# 16-channel-EEG-SCH.net
KiCad netlist of a schematic drawn in Altium Designer
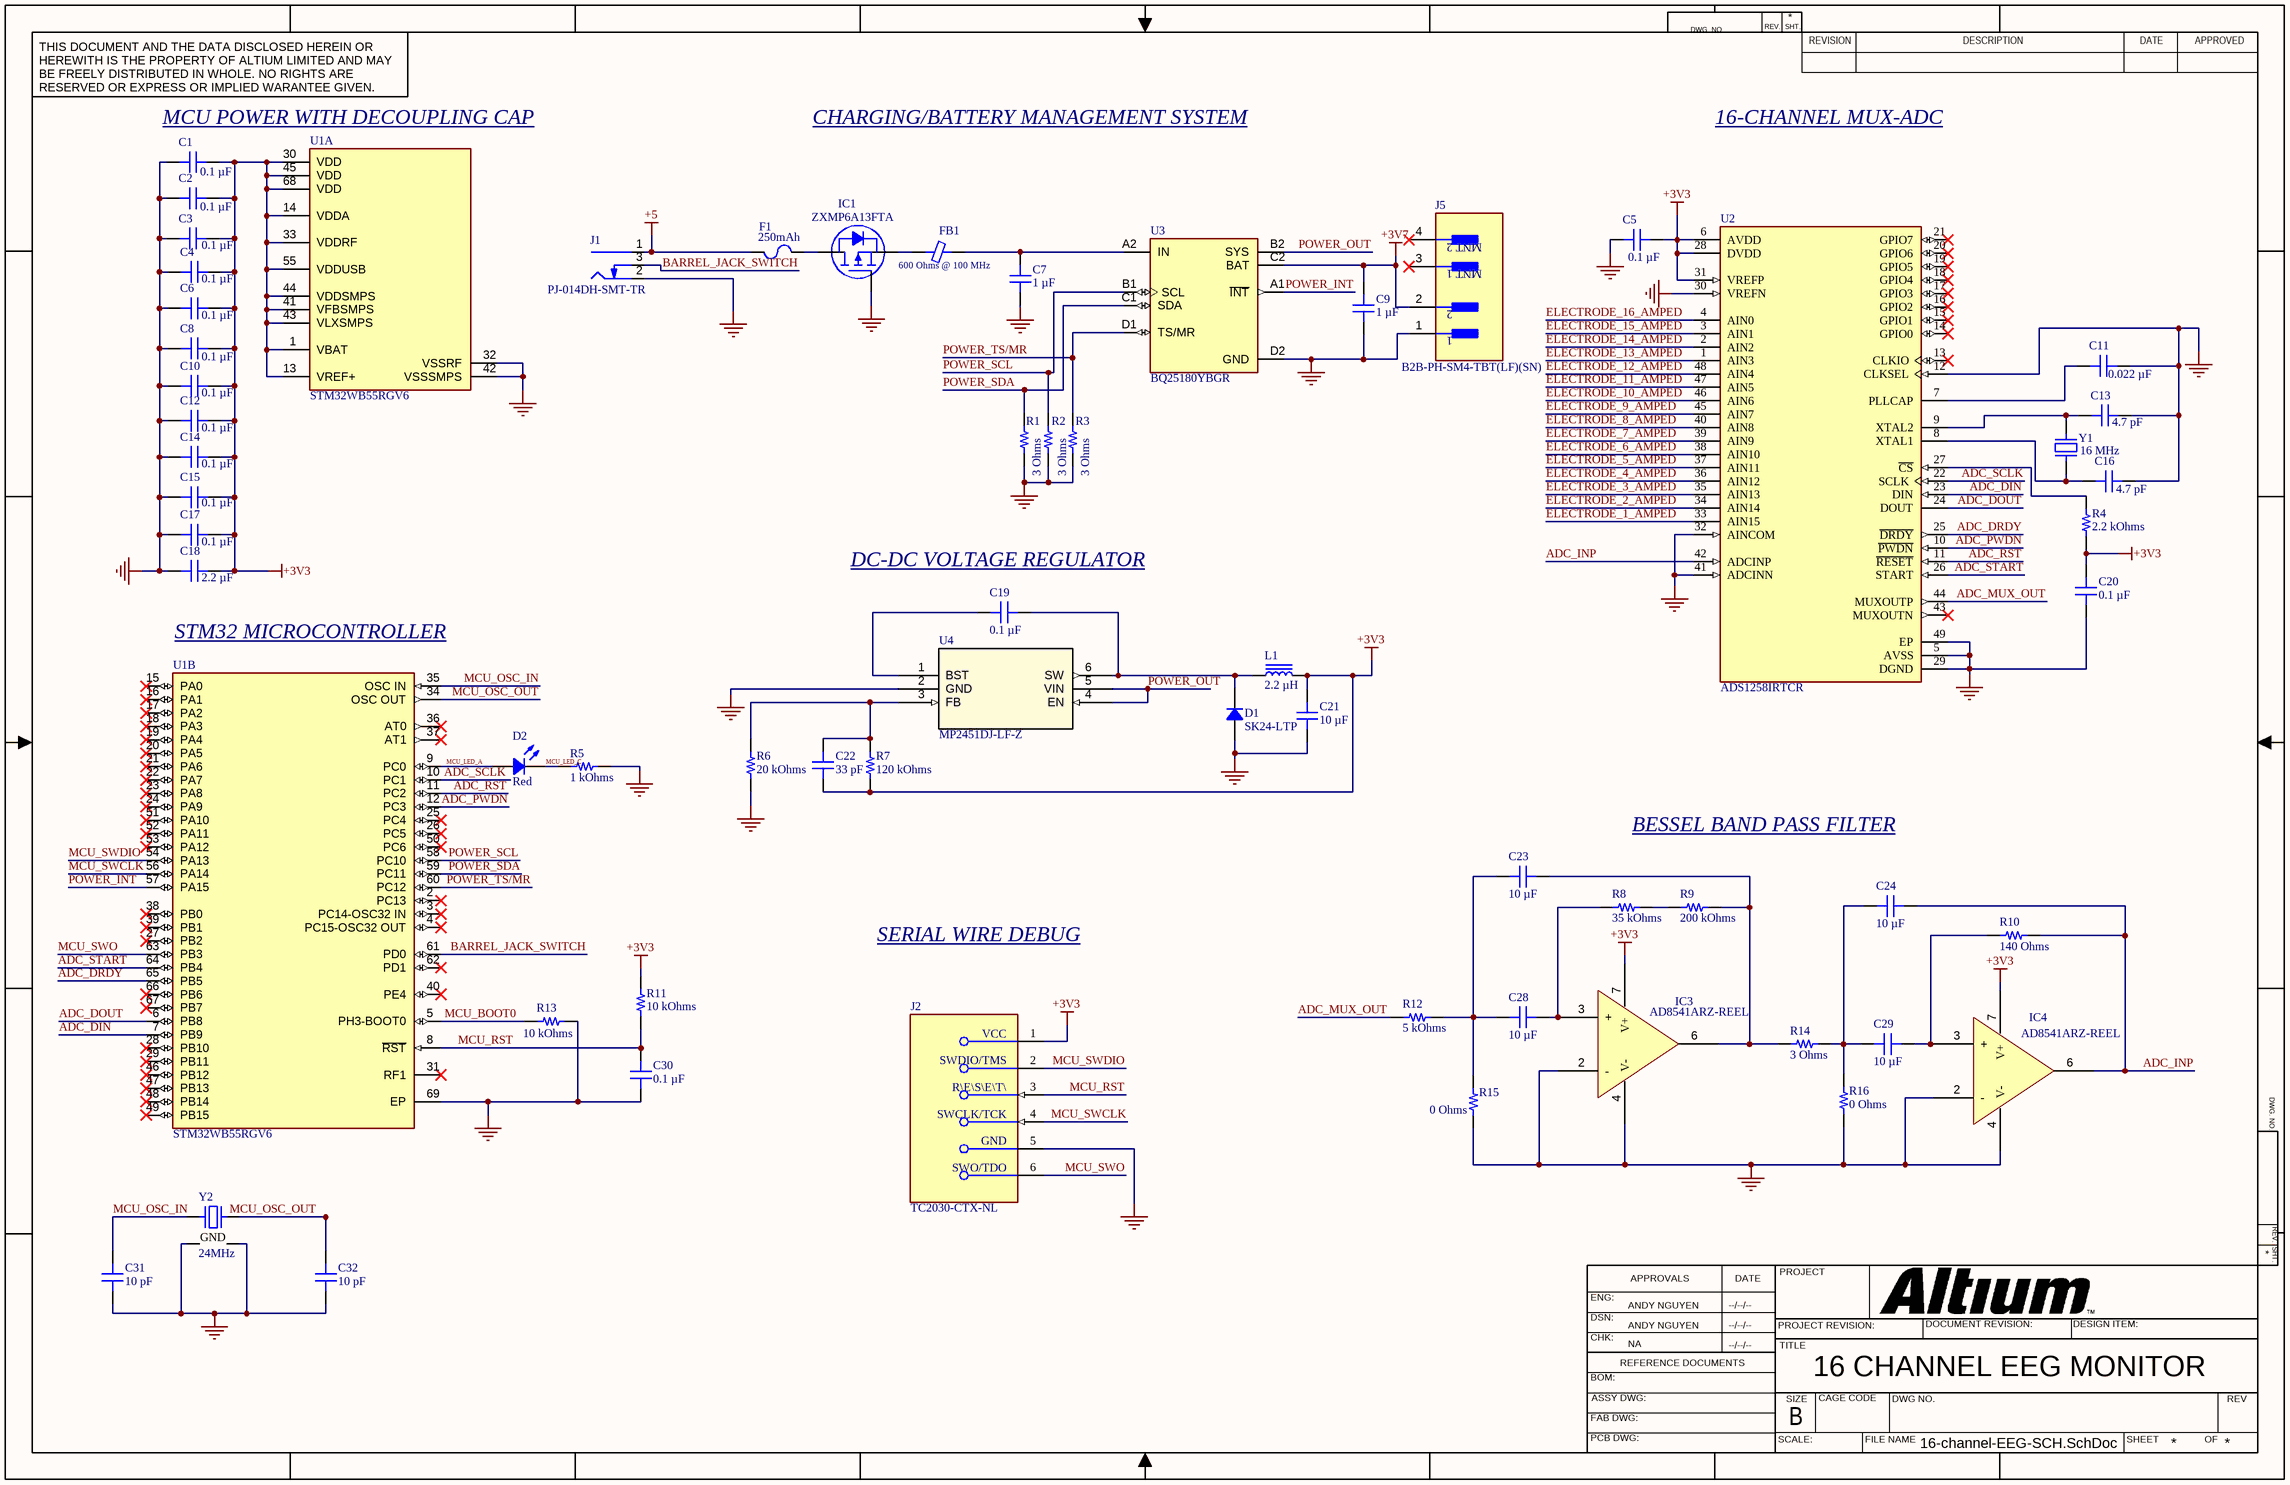
[diagram p0: 16-channel-EEG-SCH.SchDoc]

(export (version "E")
  (design (tool "Eeschema 10.0.6"))
  (components
    (comp (ref "C1")
      (value "0.1 µF")
      (footprint "CAP 0402_1005")
      (description "CAP CER 0402 0.1UF 16V X7R 10%")
      (fields (field (name "PART NUMBER") "C0402C104K4RECAUTO") (field (name "MANUFACTURER") "KEMET"))
      (libsource (lib "Celestial Altium Library - altium_library") (part "Capacitor"))
    )
    (comp (ref "C2")
      (value "0.1 µF")
      (footprint "CAP 0402_1005")
      (description "CAP CER 0402 0.1UF 16V X7R 10%")
      (fields (field (name "PART NUMBER") "C0402C104K4RECAUTO") (field (name "MANUFACTURER") "KEMET"))
      (libsource (lib "Celestial Altium Library - altium_library") (part "Capacitor"))
    )
    (comp (ref "C3")
      (value "0.1 µF")
      (footprint "CAP 0402_1005")
      (description "CAP CER 0402 0.1UF 16V X7R 10%")
      (fields (field (name "PART NUMBER") "C0402C104K4RECAUTO") (field (name "MANUFACTURER") "KEMET"))
      (libsource (lib "Celestial Altium Library - altium_library") (part "Capacitor"))
    )
    (comp (ref "C4")
      (value "0.1 µF")
      (footprint "CAP 0402_1005")
      (description "CAP CER 0402 0.1UF 16V X7R 10%")
      (fields (field (name "PART NUMBER") "C0402C104K4RECAUTO") (field (name "MANUFACTURER") "KEMET"))
      (libsource (lib "Celestial Altium Library - altium_library") (part "Capacitor"))
    )
    (comp (ref "C5")
      (value "0.1 µF")
      (footprint "CAP 0402_1005")
      (description "CAP CER 0402 0.1UF 16V X7R 10%")
      (fields (field (name "PART NUMBER") "C0402C104K4RECAUTO") (field (name "MANUFACTURER") "KEMET"))
      (libsource (lib "Celestial Altium Library - altium_library") (part "Capacitor"))
    )
    (comp (ref "C6")
      (value "0.1 µF")
      (footprint "CAP 0402_1005")
      (description "CAP CER 0402 0.1UF 16V X7R 10%")
      (fields (field (name "PART NUMBER") "C0402C104K4RECAUTO") (field (name "MANUFACTURER") "KEMET"))
      (libsource (lib "Celestial Altium Library - altium_library") (part "Capacitor"))
    )
    (comp (ref "C7")
      (value "1 µF")
      (footprint "CAP 0402_1005")
      (description "CAP CER 1UF 35V X5R 0402")
      (fields
        (field (name "PART NUMBER") "GRM155R6YA105KE11D")
        (field (name "MANUFACTURER") "Murata Electronics")
      )
      (libsource (lib "Celestial Altium Library - altium_library") (part "Capacitor"))
    )
    (comp (ref "C8")
      (value "0.1 µF")
      (footprint "CAP 0402_1005")
      (description "CAP CER 0402 0.1UF 16V X7R 10%")
      (fields (field (name "PART NUMBER") "C0402C104K4RECAUTO") (field (name "MANUFACTURER") "KEMET"))
      (libsource (lib "Celestial Altium Library - altium_library") (part "Capacitor"))
    )
    (comp (ref "C9")
      (value "1 µF")
      (footprint "CAP 0402_1005")
      (description "CAP CER 1UF 35V X5R 0402")
      (fields
        (field (name "PART NUMBER") "GRM155R6YA105KE11D")
        (field (name "MANUFACTURER") "Murata Electronics")
      )
      (libsource (lib "Celestial Altium Library - altium_library") (part "Capacitor"))
    )
    (comp (ref "C10")
      (value "0.1 µF")
      (footprint "CAP 0402_1005")
      (description "CAP CER 0402 0.1UF 16V X7R 10%")
      (fields (field (name "PART NUMBER") "C0402C104K4RECAUTO") (field (name "MANUFACTURER") "KEMET"))
      (libsource (lib "Celestial Altium Library - altium_library") (part "Capacitor"))
    )
    (comp (ref "C11")
      (value "0.022 µF")
      (footprint "CAP 0402_1005")
      (description "CAP CER 0402 22NF 16V X7R 10%")
      (fields (field (name "PART NUMBER") "C0402C223K4RECAUTO") (field (name "MANUFACTURER") "KEMET"))
      (libsource (lib "Celestial Altium Library - altium_library") (part "Capacitor"))
    )
    (comp (ref "C12")
      (value "0.1 µF")
      (footprint "CAP 0402_1005")
      (description "CAP CER 0402 0.1UF 16V X7R 10%")
      (fields (field (name "PART NUMBER") "C0402C104K4RECAUTO") (field (name "MANUFACTURER") "KEMET"))
      (libsource (lib "Celestial Altium Library - altium_library") (part "Capacitor"))
    )
    (comp (ref "C13")
      (value "4.7 pF")
      (footprint "CAP 0402_1005")
      (description "CAP CER 4.7PF 16V C0G/NP0 0402")
      (fields (field (name "PART NUMBER") "885012005023") (field (name "MANUFACTURER") "Würth Elektronik"))
      (libsource (lib "Celestial Altium Library - altium_library") (part "Capacitor"))
    )
    (comp (ref "C14")
      (value "0.1 µF")
      (footprint "CAP 0402_1005")
      (description "CAP CER 0402 0.1UF 16V X7R 10%")
      (fields (field (name "PART NUMBER") "C0402C104K4RECAUTO") (field (name "MANUFACTURER") "KEMET"))
      (libsource (lib "Celestial Altium Library - altium_library") (part "Capacitor"))
    )
    (comp (ref "C15")
      (value "0.1 µF")
      (footprint "CAP 0402_1005")
      (description "CAP CER 0402 0.1UF 16V X7R 10%")
      (fields (field (name "PART NUMBER") "C0402C104K4RECAUTO") (field (name "MANUFACTURER") "KEMET"))
      (libsource (lib "Celestial Altium Library - altium_library") (part "Capacitor"))
    )
    (comp (ref "C16")
      (value "4.7 pF")
      (footprint "CAP 0402_1005")
      (description "CAP CER 4.7PF 16V C0G/NP0 0402")
      (fields (field (name "PART NUMBER") "885012005023") (field (name "MANUFACTURER") "Würth Elektronik"))
      (libsource (lib "Celestial Altium Library - altium_library") (part "Capacitor"))
    )
    (comp (ref "C17")
      (value "0.1 µF")
      (footprint "CAP 0402_1005")
      (description "CAP CER 0402 0.1UF 16V X7R 10%")
      (fields (field (name "PART NUMBER") "C0402C104K4RECAUTO") (field (name "MANUFACTURER") "KEMET"))
      (libsource (lib "Celestial Altium Library - altium_library") (part "Capacitor"))
    )
    (comp (ref "C18")
      (value "2.2 µF")
      (footprint "CAP 0603_1608")
      (description "CAP CER 2.2UF 16V Y5V 0603")
      (fields (field (name "PART NUMBER") "CC0603ZRY5V7BB225") (field (name "MANUFACTURER") "Yageo"))
      (libsource (lib "Celestial Altium Library - altium_library") (part "Capacitor"))
    )
    (comp (ref "C19")
      (value "0.1 µF")
      (footprint "CAP 0402_1005")
      (description "CAP CER 0.1UF 100V X5R 0402")
      (fields
        (field (name "PART NUMBER") "GRM155R62A104ME14D")
        (field (name "MANUFACTURER") "Murata Electronics")
      )
      (libsource (lib "Celestial Altium Library - altium_library") (part "Capacitor"))
    )
    (comp (ref "C20")
      (value "0.1 µF")
      (footprint "CAP 0402_1005")
      (description "CAP CER 0402 0.1UF 16V X7R 10%")
      (fields (field (name "PART NUMBER") "C0402C104K4RECAUTO") (field (name "MANUFACTURER") "KEMET"))
      (libsource (lib "Celestial Altium Library - altium_library") (part "Capacitor"))
    )
    (comp (ref "C21")
      (value "10 µF")
      (footprint "CAP 0402_1005")
      (description "CAP CER 10UF 10V X5R 0402")
      (fields
        (field (name "PART NUMBER") "CL05A106MP5NUNC")
        (field (name "MANUFACTURER") "Samsung Electro-Mechanics")
      )
      (libsource (lib "Celestial Altium Library - altium_library") (part "Capacitor"))
    )
    (comp (ref "C22")
      (value "33 pF")
      (footprint "CAP 0402_1005")
      (description "CAP CER 33PF 50V CH 0402")
      (fields (field (name "PART NUMBER") "UMK105CH330JVHF") (field (name "MANUFACTURER") "Taiyo Yuden"))
      (libsource (lib "Celestial Altium Library - altium_library") (part "Capacitor"))
    )
    (comp (ref "C23")
      (value "10 µF")
      (footprint "CAP 0402_1005")
      (description "CAP CER 10UF 10V X5R 0402")
      (fields
        (field (name "PART NUMBER") "CL05A106MP5NUNC")
        (field (name "MANUFACTURER") "Samsung Electro-Mechanics")
      )
      (libsource (lib "Celestial Altium Library - altium_library") (part "Capacitor"))
    )
    (comp (ref "C24")
      (value "10 µF")
      (footprint "CAP 0402_1005")
      (description "CAP CER 10UF 10V X5R 0402")
      (fields
        (field (name "PART NUMBER") "CL05A106MP5NUNC")
        (field (name "MANUFACTURER") "Samsung Electro-Mechanics")
      )
      (libsource (lib "Celestial Altium Library - altium_library") (part "Capacitor"))
    )
    (comp (ref "C28")
      (value "10 µF")
      (footprint "CAP 0402_1005")
      (description "CAP CER 10UF 10V X5R 0402")
      (fields
        (field (name "PART NUMBER") "CL05A106MP5NUNC")
        (field (name "MANUFACTURER") "Samsung Electro-Mechanics")
      )
      (libsource (lib "Celestial Altium Library - altium_library") (part "Capacitor"))
    )
    (comp (ref "C29")
      (value "10 µF")
      (footprint "CAP 0402_1005")
      (description "CAP CER 10UF 10V X5R 0402")
      (fields
        (field (name "PART NUMBER") "CL05A106MP5NUNC")
        (field (name "MANUFACTURER") "Samsung Electro-Mechanics")
      )
      (libsource (lib "Celestial Altium Library - altium_library") (part "Capacitor"))
    )
    (comp (ref "C30")
      (value "0.1 µF")
      (footprint "CAP 0402_1005")
      (description "CAP CER 100NF 10V X7R 0402")
      (fields
        (field (name "PART NUMBER") "CL05B104KP5VPNC")
        (field (name "MANUFACTURER") "Samsung Electro-Mechanics")
      )
      (libsource (lib "Celestial Altium Library - altium_library") (part "Capacitor"))
    )
    (comp (ref "C31")
      (value "10 pF")
      (footprint "CAP 0402_1005")
      (description "CAP CER 10PF 16V C0G/NP0 0402")
      (fields (field (name "PART NUMBER") "885012005025") (field (name "MANUFACTURER") "Würth Elektronik"))
      (libsource (lib "Celestial Altium Library - altium_library") (part "Capacitor"))
    )
    (comp (ref "C32")
      (value "10 pF")
      (footprint "CAP 0402_1005")
      (description "CAP CER 10PF 16V C0G/NP0 0402")
      (fields (field (name "PART NUMBER") "885012005025") (field (name "MANUFACTURER") "Würth Elektronik"))
      (libsource (lib "Celestial Altium Library - altium_library") (part "Capacitor"))
    )
    (comp (ref "D1")
      (value "SK24-LTP")
      (footprint "DO214AA SMB")
      (description "DIODE SCHOT 40V 2A DO214AA HSMB")
      (fields (field (name "MANUFACTURER") "Micro Commercial Co"))
      (libsource (lib "Celestial Altium Library - altium_library") (part "Diode"))
    )
    (comp (ref "D2")
      (value "Red")
      (footprint "LED 1206_3216 RED")
      (description "LED SMD")
      (fields (field (name "PART NUMBER") "APTR3216SECK/J3-PRV") (field (name "MANUFACTURER") "Kingbright"))
      (libsource (lib "Celestial Altium Library - altium_library") (part "LED"))
    )
    (comp (ref "F1")
      (value "250mAh")
      (footprint "FUSE 1206_3216 0.6MM")
      (description "FUSE BOARD MNT 500MA 63VDC 1206")
      (fields (field (name "PART NUMBER") "SF-1206FP050-2") (field (name "MANUFACTURER") "Bourns Inc."))
      (libsource (lib "Celestial Altium Library - altium_library") (part "MOUNTED FUSE"))
    )
    (comp (ref "FB1")
      (value "600 Ohms @ 100 MHz")
      (footprint "FER 0805_2012")
      (description "FERRITE BEAD 600 OHM 0805 1LN")
      (fields
        (field (name "PART NUMBER") "BMB2A0600RS2")
        (field (name "MANUFACTURER") "TE Connectivity Passive Product")
      )
      (libsource (lib "Celestial Altium Library - altium_library") (part "Ferrite Chip"))
    )
    (comp (ref "IC1")
      (value "ZXMP6A13FTA")
      (footprint "DIODES SOT-23-3")
      (description "MOSFET P-CH 60V 900MA SOT23-3")
      (fields (field (name "MANUFACTURER") "Diodes Incorporated"))
      (libsource (lib "Celestial Altium Library - altium_library") (part "DIODES MOSFET P-CH SOT-23-3"))
    )
    (comp (ref "IC3")
      (value "AD8541ARZ-REEL")
      (footprint "ANALOG DEV SOIC-8 R8")
      (description "IC OPAMP GP 1 CIRCUIT 8SOIC")
      (fields (field (name "MANUFACTURER") "Analog Devices Inc."))
      (libsource (lib "Celestial Altium Library - altium_library") (part "ANALOG DEV AD8541 R"))
    )
    (comp (ref "IC4")
      (value "AD8541ARZ-REEL")
      (footprint "ANALOG DEV SOIC-8 R8")
      (description "IC OPAMP GP 1 CIRCUIT 8SOIC")
      (fields (field (name "MANUFACTURER") "Analog Devices Inc."))
      (libsource (lib "Celestial Altium Library - altium_library") (part "ANALOG DEV AD8541 R"))
    )
    (comp (ref "J1")
      (value "PJ-014DH-SMT-TR")
      (footprint "CUI PJ-014DH-SMT")
      (description "CONN PWR JACK 1.3X3.4MM SOLDER")
      (fields (field (name "MANUFACTURER") "CUI Devices"))
      (libsource (lib "Celestial Altium Library - altium_library") (part "Barrel Connector"))
    )
    (comp (ref "J2")
      (value "TC2030-CTX-NL")
      (footprint "FP-TC2030-CTX-NL-MFG")
      (description "6-Pin “No legs” TC2030 Plug-of-Nails™ Cable for use with ARM Cortex processors")
      (libsource (lib "Altium Content Vault") (part "e3fe093a55dc37473f431e03719485e"))
    )
    (comp (ref "J5")
      (value "B2B-PH-SM4-TBT(LF)(SN)")
      (footprint "FP-B2B-PH-SM4-TBT_LF_SN-MFG")
      (description "Connector Header Surface Mount 2 position 0.079\" (2.00mm)")
      (fields (field (name "OCTOPART") "https://octopart.com/b2b-ph-sm4-tbt%28lf%29%28sn%29-jst-7877930"))
      (libsource (lib "Altium Content Vault") (part "56ec3178a87b3978bdc1b3682cd516a"))
    )
    (comp (ref "L1")
      (value "2.2 µH")
      (footprint "BOURNS SRP5030T")
      (description "FIXED IND 2.2UH 5.5A 35 MOHM SMD")
      (fields (field (name "PART NUMBER") "SRP5030T-2R2M") (field (name "MANUFACTURER") "Bourns Inc."))
      (libsource (lib "Celestial Altium Library - altium_library") (part "Inductor"))
    )
    (comp (ref "R1")
      (value "3 Ohms")
      (footprint "RES 0402_1005")
      (description "RES SMD 3 OHM 5% 1/10W 0402")
      (fields
        (field (name "PART NUMBER") "ERJ-2GEJ3R0X")
        (field (name "MANUFACTURER") "Panasonic Electronic Components")
      )
      (libsource (lib "Celestial Altium Library - altium_library") (part "Resistor"))
    )
    (comp (ref "R2")
      (value "3 Ohms")
      (footprint "RES 0402_1005")
      (description "RES SMD 3 OHM 5% 1/10W 0402")
      (fields
        (field (name "PART NUMBER") "ERJ-2GEJ3R0X")
        (field (name "MANUFACTURER") "Panasonic Electronic Components")
      )
      (libsource (lib "Celestial Altium Library - altium_library") (part "Resistor"))
    )
    (comp (ref "R3")
      (value "3 Ohms")
      (footprint "RES 0402_1005")
      (description "RES SMD 3 OHM 5% 1/10W 0402")
      (fields
        (field (name "PART NUMBER") "ERJ-2GEJ3R0X")
        (field (name "MANUFACTURER") "Panasonic Electronic Components")
      )
      (libsource (lib "Celestial Altium Library - altium_library") (part "Resistor"))
    )
    (comp (ref "R4")
      (value "2.2 kOhms")
      (footprint "RES 0402_1005")
      (description "RES 2.2K OHM 0.1% 1/16W 0402")
      (fields (field (name "PART NUMBER") "TNPW04022K20BYEP") (field (name "MANUFACTURER") "Vishay Dale"))
      (libsource (lib "Celestial Altium Library - altium_library") (part "Resistor"))
    )
    (comp (ref "R5")
      (value "1 kOhms")
      (footprint "RES 0402_1005")
      (description "RES SMD 1K OHM 0.1% 1/16W 0402")
      (fields (field (name "PART NUMBER") "AT0402BRD071KL") (field (name "MANUFACTURER") "Yageo"))
      (libsource (lib "Celestial Altium Library - altium_library") (part "Resistor"))
    )
    (comp (ref "R6")
      (value "20 kOhms")
      (footprint "RES 0402_1005")
      (description "RES SMD 20K OHM 0.1% 1/16W 0402")
      (fields
        (field (name "PART NUMBER") "CPF0402B20KE")
        (field (name "MANUFACTURER") "TE Connectivity Passive Product")
      )
      (libsource (lib "Celestial Altium Library - altium_library") (part "Resistor"))
    )
    (comp (ref "R7")
      (value "120 kOhms")
      (footprint "RES 0402_1005")
      (description "RES 120K OHM 1% 1/16W 0402")
      (fields (field (name "PART NUMBER") "RC0402FR-07120KL") (field (name "MANUFACTURER") "Yageo"))
      (libsource (lib "Celestial Altium Library - altium_library") (part "Resistor"))
    )
    (comp (ref "R8")
      (value "35 kOhms")
      (footprint "RES 0402_1005")
      (description "RES 35K OHM 1% 1/16W 0402")
      (fields (field (name "PART NUMBER") "RC0402FR-0735KL") (field (name "MANUFACTURER") "Yageo"))
      (libsource (lib "Celestial Altium Library - altium_library") (part "Resistor"))
    )
    (comp (ref "R9")
      (value "200 kOhms")
      (footprint "RES 0402_1005")
      (description "RES 200K OHM 0.1% 1/10W 0402")
      (fields
        (field (name "PART NUMBER") "RP73PF1E200KBTD")
        (field (name "MANUFACTURER") "TE Connectivity Passive Product")
      )
      (libsource (lib "Celestial Altium Library - altium_library") (part "Resistor"))
    )
    (comp (ref "R10")
      (value "140 Ohms")
      (footprint "RES 0402_1005")
      (description "RES SMD 140 OHM 0.1% 1/16W 0402")
      (fields (field (name "PART NUMBER") "RT0402BRD07140RL") (field (name "MANUFACTURER") "Yageo"))
      (libsource (lib "Celestial Altium Library - altium_library") (part "Resistor"))
    )
    (comp (ref "R11")
      (value "10 kOhms")
      (footprint "RES 0402_1005")
      (description "RES 10K OHM 0.1% 1/10W 0402")
      (fields
        (field (name "PART NUMBER") "RP73PF1E10KBTD")
        (field (name "MANUFACTURER") "TE Connectivity Passive Product")
      )
      (libsource (lib "Celestial Altium Library - altium_library") (part "Resistor"))
    )
    (comp (ref "R12")
      (value "5 kOhms")
      (footprint "RES 0402_1005")
      (description "RES 5K OHM 1% 1/16W 0402")
      (fields (field (name "PART NUMBER") "RC0402FR-075KL") (field (name "MANUFACTURER") "Yageo"))
      (libsource (lib "Celestial Altium Library - altium_library") (part "Resistor"))
    )
    (comp (ref "R13")
      (value "10 kOhms")
      (footprint "RES 0402_1005")
      (description "RES 10K OHM 0.1% 1/10W 0402")
      (fields
        (field (name "PART NUMBER") "RP73PF1E10KBTD")
        (field (name "MANUFACTURER") "TE Connectivity Passive Product")
      )
      (libsource (lib "Celestial Altium Library - altium_library") (part "Resistor"))
    )
    (comp (ref "R14")
      (value "3 Ohms")
      (footprint "RES 0402_1005")
      (description "RES SMD 3 OHM 5% 1/10W 0402")
      (fields
        (field (name "PART NUMBER") "ERJ-2GEJ3R0X")
        (field (name "MANUFACTURER") "Panasonic Electronic Components")
      )
      (libsource (lib "Celestial Altium Library - altium_library") (part "Resistor"))
    )
    (comp (ref "R15")
      (value "0 Ohms")
      (footprint "RES 0402_1005")
      (description "RES 0 OHM JUMPER 1/16W 0402")
      (fields (field (name "PART NUMBER") "PA0402-R-070RL") (field (name "MANUFACTURER") "Yageo"))
      (libsource (lib "Celestial Altium Library - altium_library") (part "Resistor"))
    )
    (comp (ref "R16")
      (value "0 Ohms")
      (footprint "RES 0402_1005")
      (description "RES 0 OHM JUMPER 1/16W 0402")
      (fields (field (name "PART NUMBER") "PA0402-R-070RL") (field (name "MANUFACTURER") "Yageo"))
      (libsource (lib "Celestial Altium Library - altium_library") (part "Resistor"))
    )
    (comp (ref "U1")
      (value "STM32WB55RGV6")
      (footprint "FP-VFQFPN-68-B029-MFG")
      (description "ULTRA-LOW-POWER DUAL CORE ARM CO")
      (fields
        (field (name "OCTOPART") "https://octopart.com/stm32wb55rgv6-stmicroelectronics-98750848")
        (field (name "MANUFACTURER") "STMicroelectronics")
      )
      (libsource (lib "Altium Content Vault") (part "1f6e54ba101fb6d44bf85b07b8541cc"))
    )
    (comp (ref "U2")
      (value "ADS1258IRTCR")
      (footprint "FP-RTC0048A-IPC_C")
      (description "IC ADC 24BIT SIGMA-DELTA 48VQFN")
      (libsource (lib "Altium Content Vault") (part "09833c370b8710f3bc488bc28e0b6a6"))
    )
    (comp (ref "U3")
      (value "BQ25180YBGR")
      (footprint "IC_BQ25180YBGR")
      (description "1-A Li-ion IÂ²C programmable charger with regulated power path in WCSP package")
      (fields (field (name "MF") "Texas Instruments"))
      (libsource (lib "BQ25180YBGR") (part "BQ25180YBGR"))
    )
    (comp (ref "U4")
      (value "MP2451DJ-LF-Z")
      (footprint "TSOT23-6_MP2451_MNP")
      (description "No Description Available")
      (fields (field (name "COPYRIGHT") "Copyright (C) 2024 Ultra Librarian. All rights reserved."))
      (libsource (lib "MP2451DJ-LF-Z") (part "MP2451DJ-LF-Z"))
    )
    (comp (ref "Y1")
      (value "16 MHz")
      (footprint "ABRACON ABLS")
      (description "CRYSTAL 16.0000MHZ 18PF SMD")
      (fields (field (name "PART NUMBER") "ABLS-16.000MHZ-B2-T") (field (name "MANUFACTURER") "Abracon LLC"))
      (libsource (lib "Celestial Altium Library - altium_library") (part "Abracon Crystal ABLS"))
    )
    (comp (ref "Y2")
      (value "24MHz")
      (footprint "ABRACON ABM8G")
      (description "CRYSTAL 24.0000MHZ 10PF SMD")
      (fields
        (field (name "PART NUMBER") "ABM8G-24.000MHZ-4Y-T3")
        (field (name "MANUFACTURER") "Abracon LLC")
      )
      (libsource (lib "Celestial Altium Library - altium_library") (part "Abracon Crystal ABM8G"))
    )
  )
  (nets
    (net (code "1") (name "+3V3") (class "Default")
      (node (ref "C1") (pin "1") (pinfunction "1_1") (pintype "passive"))
      (node (ref "C10") (pin "1") (pinfunction "1_1") (pintype "passive"))
      (node (ref "C12") (pin "1") (pinfunction "1_1") (pintype "passive"))
      (node (ref "C14") (pin "1") (pinfunction "1_1") (pintype "passive"))
      (node (ref "C15") (pin "1") (pinfunction "1_1") (pintype "passive"))
      (node (ref "C17") (pin "1") (pinfunction "1_1") (pintype "passive"))
      (node (ref "C18") (pin "1") (pinfunction "1_1") (pintype "passive"))
      (node (ref "C2") (pin "1") (pinfunction "1_1") (pintype "passive"))
      (node (ref "C20") (pin "2") (pinfunction "2_2") (pintype "passive"))
      (node (ref "C21") (pin "2") (pinfunction "2_2") (pintype "passive"))
      (node (ref "C22") (pin "1") (pinfunction "1_1") (pintype "passive"))
      (node (ref "C3") (pin "1") (pinfunction "1_1") (pintype "passive"))
      (node (ref "C4") (pin "1") (pinfunction "1_1") (pintype "passive"))
      (node (ref "C5") (pin "2") (pinfunction "2_2") (pintype "passive"))
      (node (ref "C6") (pin "1") (pinfunction "1_1") (pintype "passive"))
      (node (ref "C8") (pin "1") (pinfunction "1_1") (pintype "passive"))
      (node (ref "IC3") (pin "7") (pinfunction "V+_7") (pintype "passive"))
      (node (ref "IC4") (pin "7") (pinfunction "V+_7") (pintype "passive"))
      (node (ref "J2") (pin "1") (pinfunction "VCC_1") (pintype "power_in"))
      (node (ref "L1") (pin "2") (pinfunction "2_2") (pintype "passive"))
      (node (ref "R11") (pin "2") (pinfunction "2_2") (pintype "passive"))
      (node (ref "R4") (pin "1") (pinfunction "1_1") (pintype "passive"))
      (node (ref "R7") (pin "1") (pinfunction "1_1") (pintype "passive"))
      (node (ref "U1") (pin "1") (pinfunction "VBAT_1") (pintype "power_in"))
      (node (ref "U1") (pin "13") (pinfunction "VREF+_13") (pintype "power_in"))
      (node (ref "U1") (pin "14") (pinfunction "VDDA_14") (pintype "power_in"))
      (node (ref "U1") (pin "30") (pinfunction "VDD_30") (pintype "power_in"))
      (node (ref "U1") (pin "33") (pinfunction "VDDRF_33") (pintype "power_in"))
      (node (ref "U1") (pin "41") (pinfunction "VFBSMPS_41") (pintype "power_in"))
      (node (ref "U1") (pin "43") (pinfunction "VLXSMPS_43") (pintype "power_in"))
      (node (ref "U1") (pin "44") (pinfunction "VDDSMPS_44") (pintype "power_in"))
      (node (ref "U1") (pin "45") (pinfunction "VDD_45") (pintype "power_in"))
      (node (ref "U1") (pin "55") (pinfunction "VDDUSB_55") (pintype "power_in"))
      (node (ref "U1") (pin "68") (pinfunction "VDD_68") (pintype "power_in"))
      (node (ref "U2") (pin "28") (pinfunction "DVDD_28") (pintype "power_in"))
      (node (ref "U2") (pin "31") (pinfunction "VREFP_31") (pintype "input"))
      (node (ref "U2") (pin "6") (pinfunction "AVDD_6") (pintype "power_in"))
    )
    (net (code "2") (name "+3V7") (class "Default")
      (node (ref "C9") (pin "2") (pinfunction "2_2") (pintype "passive"))
      (node (ref "J5") (pin "2") (pinfunction "2_2") (pintype "passive"))
      (node (ref "U3") (pin "C2") (pinfunction "BAT_C2") (pintype "power_in"))
    )
    (net (code "3") (name "+5") (class "Default")
      (node (ref "F1") (pin "1") (pintype "passive"))
      (node (ref "J1") (pin "1") (pinfunction "Centre_1") (pintype "passive"))
    )
    (net (code "4") (name "/ADC_DIN") (class "Default")
      (node (ref "U1") (pin "7") (pinfunction "PB9_7") (pintype "bidirectional"))
      (node (ref "U2") (pin "23") (pinfunction "DIN_23") (pintype "input"))
    )
    (net (code "5") (name "/ADC_DOUT") (class "Default")
      (node (ref "U1") (pin "6") (pinfunction "PB8_6") (pintype "bidirectional"))
      (node (ref "U2") (pin "24") (pinfunction "DOUT_24") (pintype "tri_state"))
    )
    (net (code "6") (name "/ADC_DRDY") (class "Default")
      (node (ref "U1") (pin "65") (pinfunction "PB5_65") (pintype "bidirectional"))
      (node (ref "U2") (pin "25") (pinfunction "~{DRDY}_25") (pintype "output"))
    )
    (net (code "7") (name "/ADC_INP") (class "Default")
      (node (ref "C24") (pin "2") (pinfunction "2_2") (pintype "passive"))
      (node (ref "IC4") (pin "6") (pinfunction "OUT_6") (pintype "passive"))
      (node (ref "R10") (pin "2") (pinfunction "2_2") (pintype "passive"))
      (node (ref "U2") (pin "42") (pinfunction "ADCINP_42") (pintype "input"))
    )
    (net (code "8") (name "/ADC_MUX_OUT") (class "Default")
      (node (ref "R12") (pin "1") (pinfunction "1_1") (pintype "passive"))
      (node (ref "U2") (pin "44") (pinfunction "MUXOUTP_44") (pintype "output"))
    )
    (net (code "9") (name "/ADC_PWDN") (class "Default")
      (node (ref "U1") (pin "12") (pinfunction "PC3_12") (pintype "bidirectional"))
      (node (ref "U2") (pin "10") (pinfunction "~{PWDN}_10") (pintype "input"))
    )
    (net (code "10") (name "/ADC_RST") (class "Default")
      (node (ref "U1") (pin "11") (pinfunction "PC2_11") (pintype "bidirectional"))
      (node (ref "U2") (pin "11") (pinfunction "~{RESET}_11") (pintype "input"))
    )
    (net (code "11") (name "/ADC_SCLK") (class "Default")
      (node (ref "U1") (pin "10") (pinfunction "PC1_10") (pintype "bidirectional"))
      (node (ref "U2") (pin "22") (pinfunction "SCLK_22") (pintype "input"))
    )
    (net (code "12") (name "/ADC_START") (class "Default")
      (node (ref "U1") (pin "64") (pinfunction "PB4_64") (pintype "bidirectional"))
      (node (ref "U2") (pin "26") (pinfunction "START_26") (pintype "input"))
    )
    (net (code "13") (name "/BARREL_JACK_SWITCH") (class "Default")
      (node (ref "J1") (pin "3") (pinfunction "SW_3") (pintype "passive"))
      (node (ref "U1") (pin "61") (pinfunction "PD0_61") (pintype "bidirectional"))
    )
    (net (code "14") (name "/ELECTRODE_1_AMPED") (class "Default")
      (node (ref "U2") (pin "33") (pinfunction "AIN15_33") (pintype "tri_state"))
    )
    (net (code "15") (name "/ELECTRODE_2_AMPED") (class "Default")
      (node (ref "U2") (pin "34") (pinfunction "AIN14_34") (pintype "tri_state"))
    )
    (net (code "16") (name "/ELECTRODE_3_AMPED") (class "Default")
      (node (ref "U2") (pin "35") (pinfunction "AIN13_35") (pintype "tri_state"))
    )
    (net (code "17") (name "/ELECTRODE_4_AMPED") (class "Default")
      (node (ref "U2") (pin "36") (pinfunction "AIN12_36") (pintype "tri_state"))
    )
    (net (code "18") (name "/ELECTRODE_5_AMPED") (class "Default")
      (node (ref "U2") (pin "37") (pinfunction "AIN11_37") (pintype "tri_state"))
    )
    (net (code "19") (name "/ELECTRODE_6_AMPED") (class "Default")
      (node (ref "U2") (pin "38") (pinfunction "AIN10_38") (pintype "tri_state"))
    )
    (net (code "20") (name "/ELECTRODE_7_AMPED") (class "Default")
      (node (ref "U2") (pin "39") (pinfunction "AIN9_39") (pintype "tri_state"))
    )
    (net (code "21") (name "/ELECTRODE_8_AMPED") (class "Default")
      (node (ref "U2") (pin "40") (pinfunction "AIN8_40") (pintype "tri_state"))
    )
    (net (code "22") (name "/ELECTRODE_9_AMPED") (class "Default")
      (node (ref "U2") (pin "45") (pinfunction "AIN7_45") (pintype "tri_state"))
    )
    (net (code "23") (name "/ELECTRODE_10_AMPED") (class "Default")
      (node (ref "U2") (pin "46") (pinfunction "AIN6_46") (pintype "tri_state"))
    )
    (net (code "24") (name "/ELECTRODE_11_AMPED") (class "Default")
      (node (ref "U2") (pin "47") (pinfunction "AIN5_47") (pintype "tri_state"))
    )
    (net (code "25") (name "/ELECTRODE_12_AMPED") (class "Default")
      (node (ref "U2") (pin "48") (pinfunction "AIN4_48") (pintype "tri_state"))
    )
    (net (code "26") (name "/ELECTRODE_13_AMPED") (class "Default")
      (node (ref "U2") (pin "1") (pinfunction "AIN3_1") (pintype "tri_state"))
    )
    (net (code "27") (name "/ELECTRODE_14_AMPED") (class "Default")
      (node (ref "U2") (pin "2") (pinfunction "AIN2_2") (pintype "tri_state"))
    )
    (net (code "28") (name "/ELECTRODE_15_AMPED") (class "Default")
      (node (ref "U2") (pin "3") (pinfunction "AIN1_3") (pintype "tri_state"))
    )
    (net (code "29") (name "/ELECTRODE_16_AMPED") (class "Default")
      (node (ref "U2") (pin "4") (pinfunction "AIN0_4") (pintype "tri_state"))
    )
    (net (code "30") (name "/MCU_BOOT0") (class "Default")
      (node (ref "R13") (pin "2") (pinfunction "2_2") (pintype "passive"))
      (node (ref "U1") (pin "5") (pinfunction "PH3-BOOT0_5") (pintype "bidirectional"))
    )
    (net (code "31") (name "/MCU_LED_A") (class "Default")
      (node (ref "D2") (pin "1") (pinfunction "1_1") (pintype "passive"))
      (node (ref "U1") (pin "9") (pinfunction "PC0_9") (pintype "bidirectional"))
    )
    (net (code "32") (name "/MCU_LED_C") (class "Default")
      (node (ref "D2") (pin "2") (pinfunction "2_2") (pintype "passive"))
      (node (ref "R5") (pin "2") (pinfunction "2_2") (pintype "passive"))
    )
    (net (code "33") (name "/MCU_OSC_IN") (class "Default")
      (node (ref "C31") (pin "2") (pinfunction "2_2") (pintype "passive"))
      (node (ref "U1") (pin "35") (pinfunction "OSC_IN_35") (pintype "input"))
      (node (ref "Y2") (pin "1") (pinfunction "1_1") (pintype "passive"))
    )
    (net (code "34") (name "/MCU_OSC_OUT") (class "Default")
      (node (ref "C32") (pin "2") (pinfunction "2_2") (pintype "passive"))
      (node (ref "U1") (pin "34") (pinfunction "OSC_OUT_34") (pintype "output"))
      (node (ref "Y2") (pin "3") (pinfunction "3_3") (pintype "passive"))
    )
    (net (code "35") (name "/MCU_RST") (class "Default")
      (node (ref "C30") (pin "2") (pinfunction "2_2") (pintype "passive"))
      (node (ref "J2") (pin "3") (pinfunction "~{RESET}_3") (pintype "input"))
      (node (ref "R11") (pin "1") (pinfunction "1_1") (pintype "passive"))
      (node (ref "U1") (pin "8") (pinfunction "~{RST}_8") (pintype "input"))
    )
    (net (code "36") (name "/MCU_SWCLK") (class "Default")
      (node (ref "J2") (pin "4") (pinfunction "SWCLK/TCK_4") (pintype "input"))
      (node (ref "U1") (pin "56") (pinfunction "PA14_56") (pintype "bidirectional"))
    )
    (net (code "37") (name "/MCU_SWDIO") (class "Default")
      (node (ref "J2") (pin "2") (pinfunction "SWDIO/TMS_2") (pintype "passive"))
      (node (ref "U1") (pin "54") (pinfunction "PA13_54") (pintype "bidirectional"))
    )
    (net (code "38") (name "/MCU_SWO") (class "Default")
      (node (ref "J2") (pin "6") (pinfunction "SWO/TDO_6") (pintype "passive"))
      (node (ref "U1") (pin "63") (pinfunction "PB3_63") (pintype "bidirectional"))
    )
    (net (code "39") (name "/POWER_INT") (class "Default")
      (node (ref "U1") (pin "57") (pinfunction "PA15_57") (pintype "bidirectional"))
      (node (ref "U3") (pin "A1") (pinfunction "~{INT}_A1") (pintype "output"))
    )
    (net (code "40") (name "/POWER_OUT") (class "Default")
      (node (ref "U3") (pin "B2") (pinfunction "SYS_B2") (pintype "power_in"))
      (node (ref "U4") (pin "4") (pinfunction "EN_4") (pintype "input"))
      (node (ref "U4") (pin "5") (pinfunction "VIN_5") (pintype "power_in"))
    )
    (net (code "41") (name "/POWER_SCL") (class "Default")
      (node (ref "R2") (pin "2") (pinfunction "2_2") (pintype "passive"))
      (node (ref "U1") (pin "58") (pinfunction "PC10_58") (pintype "bidirectional"))
      (node (ref "U3") (pin "B1") (pinfunction "SCL_B1") (pintype "bidirectional"))
    )
    (net (code "42") (name "/POWER_SDA") (class "Default")
      (node (ref "R1") (pin "2") (pinfunction "2_2") (pintype "passive"))
      (node (ref "U1") (pin "59") (pinfunction "PC11_59") (pintype "bidirectional"))
      (node (ref "U3") (pin "C1") (pinfunction "SDA_C1") (pintype "bidirectional"))
    )
    (net (code "43") (name "/POWER_TS{slash}MR") (class "Default")
      (node (ref "R3") (pin "2") (pinfunction "2_2") (pintype "passive"))
      (node (ref "U1") (pin "60") (pinfunction "PC12_60") (pintype "bidirectional"))
      (node (ref "U3") (pin "D1") (pinfunction "TS/MR_D1") (pintype "bidirectional"))
    )
    (net (code "44") (name "GND") (class "Default")
      (node (ref "C1") (pin "2") (pinfunction "2_2") (pintype "passive"))
      (node (ref "C10") (pin "2") (pinfunction "2_2") (pintype "passive"))
      (node (ref "C11") (pin "2") (pinfunction "2_2") (pintype "passive"))
      (node (ref "C12") (pin "2") (pinfunction "2_2") (pintype "passive"))
      (node (ref "C13") (pin "2") (pinfunction "2_2") (pintype "passive"))
      (node (ref "C14") (pin "2") (pinfunction "2_2") (pintype "passive"))
      (node (ref "C15") (pin "2") (pinfunction "2_2") (pintype "passive"))
      (node (ref "C16") (pin "2") (pinfunction "2_2") (pintype "passive"))
      (node (ref "C17") (pin "2") (pinfunction "2_2") (pintype "passive"))
      (node (ref "C18") (pin "2") (pinfunction "2_2") (pintype "passive"))
      (node (ref "C2") (pin "2") (pinfunction "2_2") (pintype "passive"))
      (node (ref "C20") (pin "1") (pinfunction "1_1") (pintype "passive"))
      (node (ref "C21") (pin "1") (pinfunction "1_1") (pintype "passive"))
      (node (ref "C3") (pin "2") (pinfunction "2_2") (pintype "passive"))
      (node (ref "C30") (pin "1") (pinfunction "1_1") (pintype "passive"))
      (node (ref "C31") (pin "1") (pinfunction "1_1") (pintype "passive"))
      (node (ref "C32") (pin "1") (pinfunction "1_1") (pintype "passive"))
      (node (ref "C4") (pin "2") (pinfunction "2_2") (pintype "passive"))
      (node (ref "C5") (pin "1") (pinfunction "1_1") (pintype "passive"))
      (node (ref "C6") (pin "2") (pinfunction "2_2") (pintype "passive"))
      (node (ref "C7") (pin "1") (pinfunction "1_1") (pintype "passive"))
      (node (ref "C8") (pin "2") (pinfunction "2_2") (pintype "passive"))
      (node (ref "C9") (pin "1") (pinfunction "1_1") (pintype "passive"))
      (node (ref "D1") (pin "1") (pinfunction "1_1") (pintype "passive"))
      (node (ref "IC1") (pin "1") (pinfunction "G_1") (pintype "passive"))
      (node (ref "IC3") (pin "2") (pinfunction "-_2") (pintype "passive"))
      (node (ref "IC3") (pin "4") (pinfunction "V-_4") (pintype "passive"))
      (node (ref "IC4") (pin "2") (pinfunction "-_2") (pintype "passive"))
      (node (ref "IC4") (pin "4") (pinfunction "V-_4") (pintype "passive"))
      (node (ref "J1") (pin "2") (pinfunction "Outer_2") (pintype "passive"))
      (node (ref "J2") (pin "5") (pinfunction "GND_5") (pintype "power_in"))
      (node (ref "J5") (pin "1") (pinfunction "1_1") (pintype "passive"))
      (node (ref "R1") (pin "1") (pinfunction "1_1") (pintype "passive"))
      (node (ref "R13") (pin "1") (pinfunction "1_1") (pintype "passive"))
      (node (ref "R15") (pin "1") (pinfunction "1_1") (pintype "passive"))
      (node (ref "R16") (pin "1") (pinfunction "1_1") (pintype "passive"))
      (node (ref "R2") (pin "1") (pinfunction "1_1") (pintype "passive"))
      (node (ref "R3") (pin "1") (pinfunction "1_1") (pintype "passive"))
      (node (ref "R5") (pin "1") (pinfunction "1_1") (pintype "passive"))
      (node (ref "R6") (pin "1") (pinfunction "1_1") (pintype "passive"))
      (node (ref "U1") (pin "32") (pinfunction "VSSRF_32") (pintype "power_in"))
      (node (ref "U1") (pin "42") (pinfunction "VSSSMPS_42") (pintype "power_in"))
      (node (ref "U1") (pin "69") (pinfunction "EP_69") (pintype "power_in"))
      (node (ref "U2") (pin "12") (pinfunction "CLKSEL_12") (pintype "input"))
      (node (ref "U2") (pin "29") (pinfunction "DGND_29") (pintype "power_in"))
      (node (ref "U2") (pin "30") (pinfunction "VREFN_30") (pintype "input"))
      (node (ref "U2") (pin "32") (pinfunction "AINCOM_32") (pintype "input"))
      (node (ref "U2") (pin "41") (pinfunction "ADCINN_41") (pintype "input"))
      (node (ref "U2") (pin "49") (pinfunction "EP_49") (pintype "power_in"))
      (node (ref "U2") (pin "5") (pinfunction "AVSS_5") (pintype "power_in"))
      (node (ref "U3") (pin "D2") (pinfunction "GND_D2") (pintype "power_in"))
      (node (ref "U4") (pin "2") (pinfunction "GND_2") (pintype "power_in"))
      (node (ref "Y2") (pin "2") (pinfunction "GND_2") (pintype "passive"))
      (node (ref "Y2") (pin "4") (pinfunction "GND_4") (pintype "passive"))
    )
    (net (code "45") (name "Net-(C23-Pad1)") (class "Default")
      (node (ref "C23") (pin "1") (pinfunction "1_1") (pintype "passive"))
      (node (ref "C28") (pin "1") (pinfunction "1_1") (pintype "passive"))
      (node (ref "R12") (pin "2") (pinfunction "2_2") (pintype "passive"))
      (node (ref "R15") (pin "2") (pinfunction "2_2") (pintype "passive"))
    )
    (net (code "46") (name "Net-(C24-Pad1)") (class "Default")
      (node (ref "C24") (pin "1") (pinfunction "1_1") (pintype "passive"))
      (node (ref "C29") (pin "1") (pinfunction "1_1") (pintype "passive"))
      (node (ref "R14") (pin "2") (pinfunction "2_2") (pintype "passive"))
      (node (ref "R16") (pin "2") (pinfunction "2_2") (pintype "passive"))
    )
    (net (code "47") (name "Net-(IC1-D)") (class "Default")
      (node (ref "F1") (pin "2") (pintype "passive"))
      (node (ref "IC1") (pin "3") (pinfunction "D_3") (pintype "passive"))
    )
    (net (code "48") (name "Net-(IC1-S)") (class "Default")
      (node (ref "FB1") (pin "1") (pinfunction "1_1") (pintype "passive"))
      (node (ref "IC1") (pin "2") (pinfunction "S_2") (pintype "passive"))
    )
    (net (code "49") (name "Net-(IC3-+)") (class "Default")
      (node (ref "C28") (pin "2") (pinfunction "2_2") (pintype "passive"))
      (node (ref "IC3") (pin "3") (pinfunction "+_3") (pintype "passive"))
      (node (ref "R8") (pin "1") (pinfunction "1_1") (pintype "passive"))
    )
    (net (code "50") (name "Net-(IC3-OUT)") (class "Default")
      (node (ref "C23") (pin "2") (pinfunction "2_2") (pintype "passive"))
      (node (ref "IC3") (pin "6") (pinfunction "OUT_6") (pintype "passive"))
      (node (ref "R14") (pin "1") (pinfunction "1_1") (pintype "passive"))
      (node (ref "R9") (pin "2") (pinfunction "2_2") (pintype "passive"))
    )
    (net (code "51") (name "Net-(IC4-+)") (class "Default")
      (node (ref "C29") (pin "2") (pinfunction "2_2") (pintype "passive"))
      (node (ref "IC4") (pin "3") (pinfunction "+_3") (pintype "passive"))
      (node (ref "R10") (pin "1") (pinfunction "1_1") (pintype "passive"))
    )
    (net (code "52") (name "Net-(R8-Pad2)") (class "Default")
      (node (ref "R8") (pin "2") (pinfunction "2_2") (pintype "passive"))
      (node (ref "R9") (pin "1") (pinfunction "1_1") (pintype "passive"))
    )
    (net (code "53") (name "Net-(U2-PLLCAP)") (class "Default")
      (node (ref "C11") (pin "1") (pinfunction "1_1") (pintype "passive"))
      (node (ref "U2") (pin "7") (pinfunction "PLLCAP_7") (pintype "passive"))
    )
    (net (code "54") (name "Net-(U2-XTAL1)") (class "Default")
      (node (ref "C16") (pin "1") (pinfunction "1_1") (pintype "passive"))
      (node (ref "U2") (pin "8") (pinfunction "XTAL1_8") (pintype "passive"))
      (node (ref "Y1") (pin "1") (pinfunction "1_1") (pintype "passive"))
    )
    (net (code "55") (name "Net-(U2-XTAL2)") (class "Default")
      (node (ref "C13") (pin "1") (pinfunction "1_1") (pintype "passive"))
      (node (ref "U2") (pin "9") (pinfunction "XTAL2_9") (pintype "passive"))
      (node (ref "Y1") (pin "2") (pinfunction "2_2") (pintype "passive"))
    )
    (net (code "56") (name "Net-(U2-~{CS})") (class "Default")
      (node (ref "R4") (pin "2") (pinfunction "2_2") (pintype "passive"))
      (node (ref "U2") (pin "27") (pinfunction "~{CS}_27") (pintype "input"))
    )
    (net (code "57") (name "Net-(U3-IN)") (class "Default")
      (node (ref "C7") (pin "2") (pinfunction "2_2") (pintype "passive"))
      (node (ref "FB1") (pin "2") (pinfunction "2_2") (pintype "passive"))
      (node (ref "U3") (pin "A2") (pinfunction "IN_A2") (pintype "power_in"))
    )
    (net (code "58") (name "Net-(U4-BST)") (class "Default")
      (node (ref "C19") (pin "1") (pinfunction "1_1") (pintype "passive"))
      (node (ref "U4") (pin "1") (pinfunction "BST_1") (pintype "power_in"))
    )
    (net (code "59") (name "Net-(U4-FB)") (class "Default")
      (node (ref "C22") (pin "2") (pinfunction "2_2") (pintype "passive"))
      (node (ref "R6") (pin "2") (pinfunction "2_2") (pintype "passive"))
      (node (ref "R7") (pin "2") (pinfunction "2_2") (pintype "passive"))
      (node (ref "U4") (pin "3") (pinfunction "FB_3") (pintype "input"))
    )
    (net (code "60") (name "Net-(U4-SW)") (class "Default")
      (node (ref "C19") (pin "2") (pinfunction "2_2") (pintype "passive"))
      (node (ref "D1") (pin "2") (pinfunction "2_2") (pintype "passive"))
      (node (ref "L1") (pin "1") (pinfunction "1_1") (pintype "passive"))
      (node (ref "U4") (pin "6") (pinfunction "SW_6") (pintype "output"))
    )
    (net (code "61") (name "unconnected-(J5-MNT_1-Pad3)") (class "Default")
      (node (ref "J5") (pin "3") (pinfunction "MNT_1_3") (pintype "passive+no_connect"))
    )
    (net (code "62") (name "unconnected-(J5-MNT_2-Pad4)") (class "Default")
      (node (ref "J5") (pin "4") (pinfunction "MNT_2_4") (pintype "passive+no_connect"))
    )
    (net (code "63") (name "unconnected-(U1B-AT0-Pad36)") (class "Default")
      (node (ref "U1") (pin "36") (pinfunction "AT0_36") (pintype "output+no_connect"))
    )
    (net (code "64") (name "unconnected-(U1B-AT1-Pad37)") (class "Default")
      (node (ref "U1") (pin "37") (pinfunction "AT1_37") (pintype "output+no_connect"))
    )
    (net (code "65") (name "unconnected-(U1B-PA0-Pad15)") (class "Default")
      (node (ref "U1") (pin "15") (pinfunction "PA0_15") (pintype "bidirectional+no_connect"))
    )
    (net (code "66") (name "unconnected-(U1B-PA1-Pad16)") (class "Default")
      (node (ref "U1") (pin "16") (pinfunction "PA1_16") (pintype "bidirectional+no_connect"))
    )
    (net (code "67") (name "unconnected-(U1B-PA2-Pad17)") (class "Default")
      (node (ref "U1") (pin "17") (pinfunction "PA2_17") (pintype "bidirectional+no_connect"))
    )
    (net (code "68") (name "unconnected-(U1B-PA3-Pad18)") (class "Default")
      (node (ref "U1") (pin "18") (pinfunction "PA3_18") (pintype "bidirectional+no_connect"))
    )
    (net (code "69") (name "unconnected-(U1B-PA4-Pad19)") (class "Default")
      (node (ref "U1") (pin "19") (pinfunction "PA4_19") (pintype "bidirectional+no_connect"))
    )
    (net (code "70") (name "unconnected-(U1B-PA5-Pad20)") (class "Default")
      (node (ref "U1") (pin "20") (pinfunction "PA5_20") (pintype "bidirectional+no_connect"))
    )
    (net (code "71") (name "unconnected-(U1B-PA6-Pad21)") (class "Default")
      (node (ref "U1") (pin "21") (pinfunction "PA6_21") (pintype "bidirectional+no_connect"))
    )
    (net (code "72") (name "unconnected-(U1B-PA7-Pad22)") (class "Default")
      (node (ref "U1") (pin "22") (pinfunction "PA7_22") (pintype "bidirectional+no_connect"))
    )
    (net (code "73") (name "unconnected-(U1B-PA8-Pad23)") (class "Default")
      (node (ref "U1") (pin "23") (pinfunction "PA8_23") (pintype "bidirectional+no_connect"))
    )
    (net (code "74") (name "unconnected-(U1B-PA9-Pad24)") (class "Default")
      (node (ref "U1") (pin "24") (pinfunction "PA9_24") (pintype "bidirectional+no_connect"))
    )
    (net (code "75") (name "unconnected-(U1B-PA10-Pad51)") (class "Default")
      (node (ref "U1") (pin "51") (pinfunction "PA10_51") (pintype "bidirectional+no_connect"))
    )
    (net (code "76") (name "unconnected-(U1B-PA11-Pad52)") (class "Default")
      (node (ref "U1") (pin "52") (pinfunction "PA11_52") (pintype "bidirectional+no_connect"))
    )
    (net (code "77") (name "unconnected-(U1B-PA12-Pad53)") (class "Default")
      (node (ref "U1") (pin "53") (pinfunction "PA12_53") (pintype "bidirectional+no_connect"))
    )
    (net (code "78") (name "unconnected-(U1B-PB0-Pad38)") (class "Default")
      (node (ref "U1") (pin "38") (pinfunction "PB0_38") (pintype "bidirectional+no_connect"))
    )
    (net (code "79") (name "unconnected-(U1B-PB1-Pad39)") (class "Default")
      (node (ref "U1") (pin "39") (pinfunction "PB1_39") (pintype "bidirectional+no_connect"))
    )
    (net (code "80") (name "unconnected-(U1B-PB2-Pad27)") (class "Default")
      (node (ref "U1") (pin "27") (pinfunction "PB2_27") (pintype "bidirectional+no_connect"))
    )
    (net (code "81") (name "unconnected-(U1B-PB6-Pad66)") (class "Default")
      (node (ref "U1") (pin "66") (pinfunction "PB6_66") (pintype "bidirectional+no_connect"))
    )
    (net (code "82") (name "unconnected-(U1B-PB7-Pad67)") (class "Default")
      (node (ref "U1") (pin "67") (pinfunction "PB7_67") (pintype "bidirectional+no_connect"))
    )
    (net (code "83") (name "unconnected-(U1B-PB10-Pad28)") (class "Default")
      (node (ref "U1") (pin "28") (pinfunction "PB10_28") (pintype "bidirectional+no_connect"))
    )
    (net (code "84") (name "unconnected-(U1B-PB11-Pad29)") (class "Default")
      (node (ref "U1") (pin "29") (pinfunction "PB11_29") (pintype "bidirectional+no_connect"))
    )
    (net (code "85") (name "unconnected-(U1B-PB12-Pad46)") (class "Default")
      (node (ref "U1") (pin "46") (pinfunction "PB12_46") (pintype "bidirectional+no_connect"))
    )
    (net (code "86") (name "unconnected-(U1B-PB13-Pad47)") (class "Default")
      (node (ref "U1") (pin "47") (pinfunction "PB13_47") (pintype "bidirectional+no_connect"))
    )
    (net (code "87") (name "unconnected-(U1B-PB14-Pad48)") (class "Default")
      (node (ref "U1") (pin "48") (pinfunction "PB14_48") (pintype "bidirectional+no_connect"))
    )
    (net (code "88") (name "unconnected-(U1B-PB15-Pad49)") (class "Default")
      (node (ref "U1") (pin "49") (pinfunction "PB15_49") (pintype "bidirectional+no_connect"))
    )
    (net (code "89") (name "unconnected-(U1B-PC4-Pad25)") (class "Default")
      (node (ref "U1") (pin "25") (pinfunction "PC4_25") (pintype "bidirectional+no_connect"))
    )
    (net (code "90") (name "unconnected-(U1B-PC5-Pad26)") (class "Default")
      (node (ref "U1") (pin "26") (pinfunction "PC5_26") (pintype "bidirectional+no_connect"))
    )
    (net (code "91") (name "unconnected-(U1B-PC6-Pad50)") (class "Default")
      (node (ref "U1") (pin "50") (pinfunction "PC6_50") (pintype "bidirectional+no_connect"))
    )
    (net (code "92") (name "unconnected-(U1B-PC13-Pad2)") (class "Default")
      (node (ref "U1") (pin "2") (pinfunction "PC13_2") (pintype "bidirectional+no_connect"))
    )
    (net (code "93") (name "unconnected-(U1B-PC14-OSC32_IN-Pad3)") (class "Default")
      (node (ref "U1") (pin "3") (pinfunction "PC14-OSC32_IN_3") (pintype "bidirectional+no_connect"))
    )
    (net (code "94") (name "unconnected-(U1B-PC15-OSC32_OUT-Pad4)") (class "Default")
      (node (ref "U1") (pin "4") (pinfunction "PC15-OSC32_OUT_4") (pintype "bidirectional+no_connect"))
    )
    (net (code "95") (name "unconnected-(U1B-PD1-Pad62)") (class "Default")
      (node (ref "U1") (pin "62") (pinfunction "PD1_62") (pintype "bidirectional+no_connect"))
    )
    (net (code "96") (name "unconnected-(U1B-PE4-Pad40)") (class "Default")
      (node (ref "U1") (pin "40") (pinfunction "PE4_40") (pintype "bidirectional+no_connect"))
    )
    (net (code "97") (name "unconnected-(U1B-RF1-Pad31)") (class "Default")
      (node (ref "U1") (pin "31") (pinfunction "RF1_31") (pintype "power_in+no_connect"))
    )
    (net (code "98") (name "unconnected-(U2-CLKIO-Pad13)") (class "Default")
      (node (ref "U2") (pin "13") (pinfunction "CLKIO_13") (pintype "bidirectional+no_connect"))
    )
    (net (code "99") (name "unconnected-(U2-GPIO0-Pad14)") (class "Default")
      (node (ref "U2") (pin "14") (pinfunction "GPIO0_14") (pintype "bidirectional+no_connect"))
    )
    (net (code "100") (name "unconnected-(U2-GPIO1-Pad15)") (class "Default")
      (node (ref "U2") (pin "15") (pinfunction "GPIO1_15") (pintype "bidirectional+no_connect"))
    )
    (net (code "101") (name "unconnected-(U2-GPIO2-Pad16)") (class "Default")
      (node (ref "U2") (pin "16") (pinfunction "GPIO2_16") (pintype "bidirectional+no_connect"))
    )
    (net (code "102") (name "unconnected-(U2-GPIO3-Pad17)") (class "Default")
      (node (ref "U2") (pin "17") (pinfunction "GPIO3_17") (pintype "bidirectional+no_connect"))
    )
    (net (code "103") (name "unconnected-(U2-GPIO4-Pad18)") (class "Default")
      (node (ref "U2") (pin "18") (pinfunction "GPIO4_18") (pintype "bidirectional+no_connect"))
    )
    (net (code "104") (name "unconnected-(U2-GPIO5-Pad19)") (class "Default")
      (node (ref "U2") (pin "19") (pinfunction "GPIO5_19") (pintype "bidirectional+no_connect"))
    )
    (net (code "105") (name "unconnected-(U2-GPIO6-Pad20)") (class "Default")
      (node (ref "U2") (pin "20") (pinfunction "GPIO6_20") (pintype "bidirectional+no_connect"))
    )
    (net (code "106") (name "unconnected-(U2-GPIO7-Pad21)") (class "Default")
      (node (ref "U2") (pin "21") (pinfunction "GPIO7_21") (pintype "bidirectional+no_connect"))
    )
    (net (code "107") (name "unconnected-(U2-MUXOUTN-Pad43)") (class "Default")
      (node (ref "U2") (pin "43") (pinfunction "MUXOUTN_43") (pintype "output+no_connect"))
    )
  )
)
